# RangkaianESP32___RangkaianDriverMotorDC.net
KiCad netlist of a schematic drawn in EAGLE
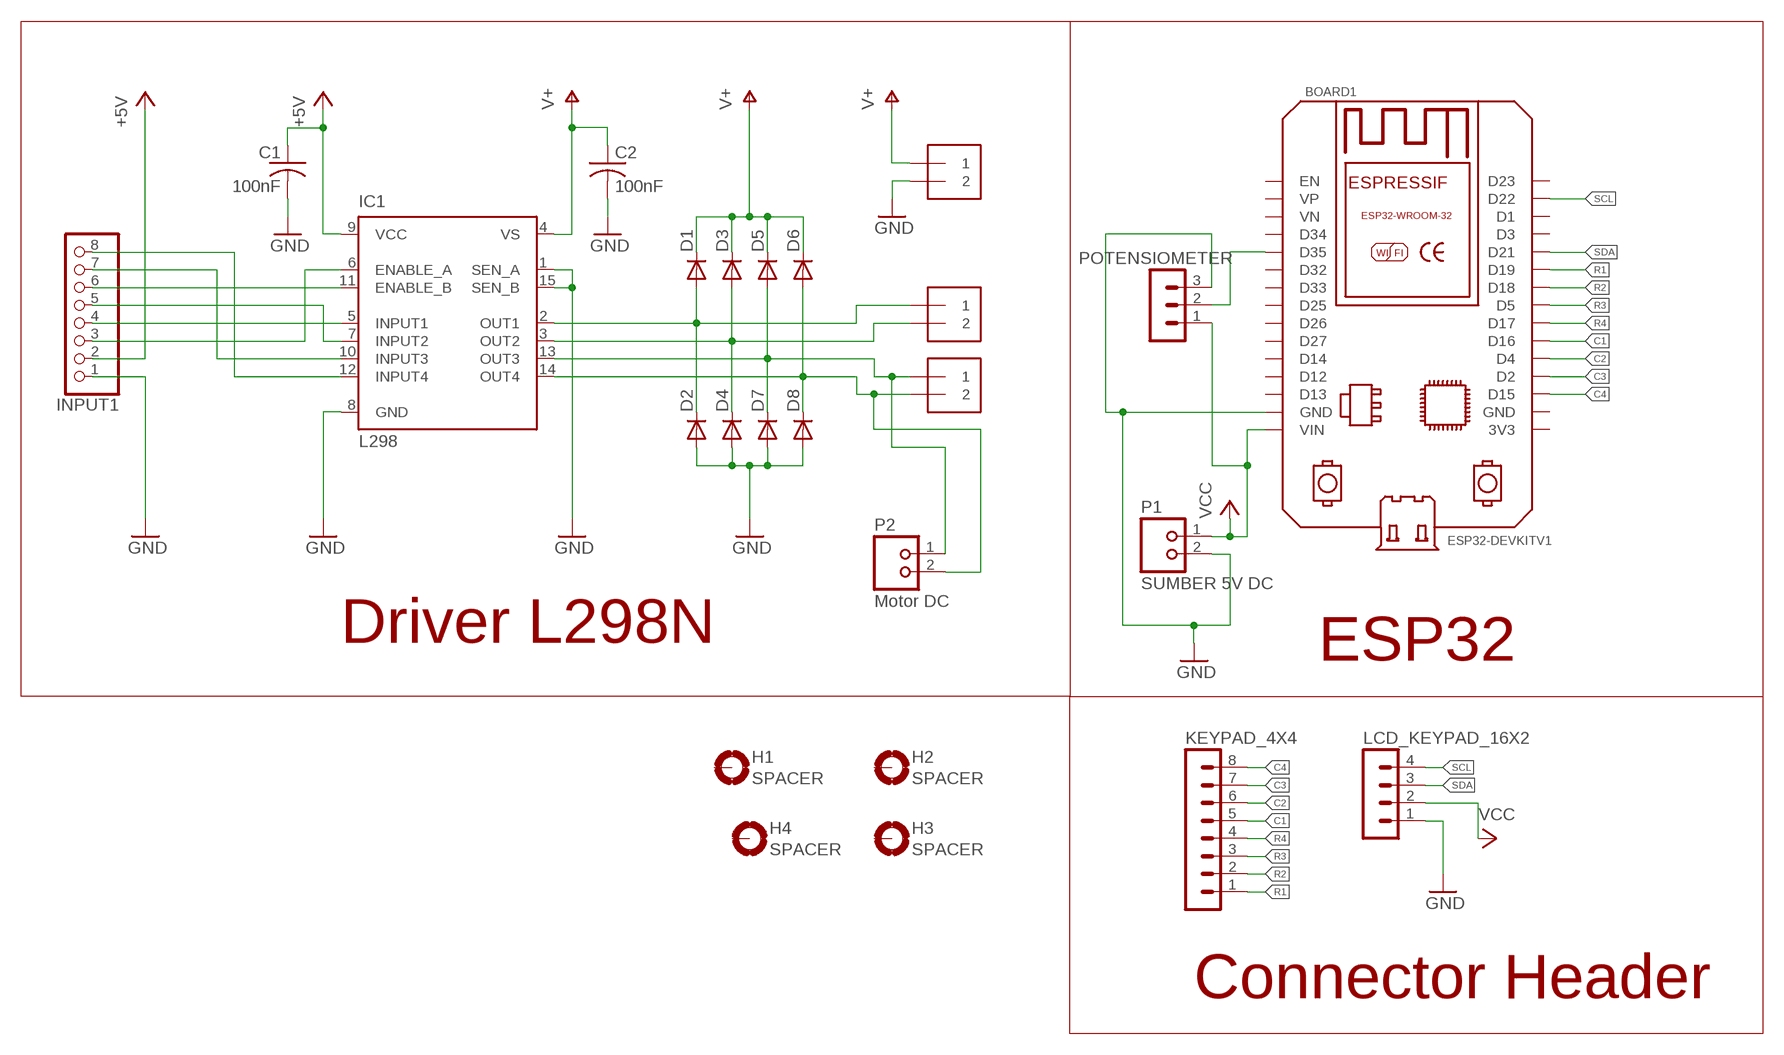
[diagram p0: schematic, sheet 1]

(export (version "E")
  (design (tool "Eeschema 10.0.6"))
  (components
    (comp (ref "BOARD1")
      (value "ESP32DEVKITV1SHRIDATTDUDHAT")
      (footprint "eagle-import:ESP32-DEVKITV1")
      (libsource (lib "eagle-import") (part "ESP32DEVKITV1SHRIDATTDUDHAT"))
    )
    (comp (ref "C1")
      (value "100nF")
      (footprint "eagle-import:C050-024X044")
      (libsource (lib "eagle-import") (part "C-US050-024X044"))
    )
    (comp (ref "C2")
      (value "100nF")
      (footprint "eagle-import:C050-024X044")
      (libsource (lib "eagle-import") (part "C-US050-024X044"))
    )
    (comp (ref "D1")
      (value "DIODE-D-5")
      (footprint "eagle-import:D-5")
      (libsource (lib "eagle-import") (part "DIODE-D-5"))
    )
    (comp (ref "D2")
      (value "DIODE-D-5")
      (footprint "eagle-import:D-5")
      (libsource (lib "eagle-import") (part "DIODE-D-5"))
    )
    (comp (ref "D3")
      (value "DIODE-D-5")
      (footprint "eagle-import:D-5")
      (libsource (lib "eagle-import") (part "DIODE-D-5"))
    )
    (comp (ref "D4")
      (value "DIODE-D-5")
      (footprint "eagle-import:D-5")
      (libsource (lib "eagle-import") (part "DIODE-D-5"))
    )
    (comp (ref "D5")
      (value "DIODE-D-5")
      (footprint "eagle-import:D-5")
      (libsource (lib "eagle-import") (part "DIODE-D-5"))
    )
    (comp (ref "D6")
      (value "DIODE-D-5")
      (footprint "eagle-import:D-5")
      (libsource (lib "eagle-import") (part "DIODE-D-5"))
    )
    (comp (ref "D7")
      (value "DIODE-D-5")
      (footprint "eagle-import:D-5")
      (libsource (lib "eagle-import") (part "DIODE-D-5"))
    )
    (comp (ref "D8")
      (value "DIODE-D-5")
      (footprint "eagle-import:D-5")
      (libsource (lib "eagle-import") (part "DIODE-D-5"))
    )
    (comp (ref "H1")
      (value "SPACER")
      (footprint "eagle-import:3,0-PAD")
      (libsource (lib "eagle-import") (part "SPACER"))
    )
    (comp (ref "H2")
      (value "SPACER")
      (footprint "eagle-import:3,0-PAD")
      (libsource (lib "eagle-import") (part "SPACER"))
    )
    (comp (ref "H3")
      (value "SPACER")
      (footprint "eagle-import:3,0-PAD")
      (libsource (lib "eagle-import") (part "SPACER"))
    )
    (comp (ref "H4")
      (value "SPACER")
      (footprint "eagle-import:3,0-PAD")
      (libsource (lib "eagle-import") (part "SPACER"))
    )
    (comp (ref "IC1")
      (value "L298")
      (footprint "eagle-import:MULTIWATT-15")
      (fields (field (name "MPN") "L298N"))
      (libsource (lib "eagle-import") (part "L298"))
    )
    (comp (ref "INPUT1")
      (value "PINHD-1X8")
      (footprint "eagle-import:1X08")
      (libsource (lib "eagle-import") (part "PINHD-1X8"))
    )
    (comp (ref "KEYPAD_4X4")
      (value "MA08-1")
      (footprint "eagle-import:MA08-1")
      (libsource (lib "eagle-import") (part "MA08-1"))
    )
    (comp (ref "LCD_KEYPAD_16X2")
      (value "MA04-1")
      (footprint "eagle-import:MA04-1")
      (libsource (lib "eagle-import") (part "MA04-1"))
    )
    (comp (ref "OUTPUT1")
      (value "1X2-3.5MM")
      (footprint "eagle-import:1X2-3.5MM")
      (libsource (lib "eagle-import") (part "1X2-3.5MM"))
    )
    (comp (ref "OUTPUT2")
      (value "1X2-3.5MM")
      (footprint "eagle-import:1X2-3.5MM")
      (libsource (lib "eagle-import") (part "1X2-3.5MM"))
    )
    (comp (ref "OUTPUT3")
      (value "1X2-3.5MM")
      (footprint "eagle-import:1X2-3.5MM")
      (libsource (lib "eagle-import") (part "1X2-3.5MM"))
    )
    (comp (ref "P1")
      (value "SUMBER 5V DC")
      (footprint "eagle-import:TERMINAL_2P")
      (libsource (lib "eagle-import") (part "T-BLOCK"))
    )
    (comp (ref "P2")
      (value "Motor DC")
      (footprint "eagle-import:TERMINAL_2P")
      (libsource (lib "eagle-import") (part "T-BLOCK"))
    )
    (comp (ref "POTENSIOMETER")
      (value "MA03-1")
      (footprint "eagle-import:MA03-1")
      (libsource (lib "eagle-import") (part "MA03-1"))
    )
  )
  (nets
    (net (code "1") (name "+5V") (class "Default")
      (node (ref "C1") (pin "1") (pinfunction "1_1") (pintype "passive"))
      (node (ref "IC1") (pin "9") (pinfunction "VCC_9") (pintype "power_in"))
      (node (ref "INPUT1") (pin "2") (pinfunction "2_2") (pintype "passive"))
    )
    (net (code "2") (name "C1") (class "Default")
      (node (ref "BOARD1") (pin "D16") (pinfunction "D16_D16") (pintype "bidirectional"))
      (node (ref "KEYPAD_4X4") (pin "5") (pinfunction "5_5") (pintype "passive"))
    )
    (net (code "3") (name "C2") (class "Default")
      (node (ref "BOARD1") (pin "D4") (pinfunction "D4_D4") (pintype "bidirectional"))
      (node (ref "KEYPAD_4X4") (pin "6") (pinfunction "6_6") (pintype "passive"))
    )
    (net (code "4") (name "C3") (class "Default")
      (node (ref "BOARD1") (pin "D2") (pinfunction "D2_D2") (pintype "bidirectional"))
      (node (ref "KEYPAD_4X4") (pin "7") (pinfunction "7_7") (pintype "passive"))
    )
    (net (code "5") (name "C4") (class "Default")
      (node (ref "BOARD1") (pin "D15") (pinfunction "D15_D15") (pintype "bidirectional"))
      (node (ref "KEYPAD_4X4") (pin "8") (pinfunction "8_8") (pintype "passive"))
    )
    (net (code "6") (name "GND") (class "Default")
      (node (ref "BOARD1") (pin "GND") (pinfunction "GND_GND") (pintype "bidirectional"))
      (node (ref "C1") (pin "2") (pinfunction "2_2") (pintype "passive"))
      (node (ref "C2") (pin "2") (pinfunction "2_2") (pintype "passive"))
      (node (ref "D2") (pin "A") (pinfunction "A_A") (pintype "passive"))
      (node (ref "D4") (pin "A") (pinfunction "A_A") (pintype "passive"))
      (node (ref "D7") (pin "A") (pinfunction "A_A") (pintype "passive"))
      (node (ref "D8") (pin "A") (pinfunction "A_A") (pintype "passive"))
      (node (ref "IC1") (pin "1") (pinfunction "SEN_A_1") (pintype "input"))
      (node (ref "IC1") (pin "15") (pinfunction "SEN_B_15") (pintype "input"))
      (node (ref "IC1") (pin "8") (pinfunction "GND_8") (pintype "power_in"))
      (node (ref "INPUT1") (pin "1") (pinfunction "1_1") (pintype "passive"))
      (node (ref "LCD_KEYPAD_16X2") (pin "1") (pinfunction "1_1") (pintype "passive"))
      (node (ref "OUTPUT1") (pin "2") (pinfunction "2_2") (pintype "passive"))
      (node (ref "P1") (pin "2") (pinfunction "2_2") (pintype "passive"))
      (node (ref "POTENSIOMETER") (pin "3") (pinfunction "3_3") (pintype "passive"))
    )
    (net (code "7") (name "Net-(BOARD1-PadD35)") (class "Default")
      (node (ref "BOARD1") (pin "D35") (pinfunction "D35_D35") (pintype "bidirectional"))
      (node (ref "POTENSIOMETER") (pin "2") (pinfunction "2_2") (pintype "passive"))
    )
    (net (code "8") (name "Net-(IC1-ENABLE_A)") (class "Default")
      (node (ref "IC1") (pin "6") (pinfunction "ENABLE_A_6") (pintype "input"))
      (node (ref "INPUT1") (pin "3") (pinfunction "3_3") (pintype "passive"))
    )
    (net (code "9") (name "Net-(IC1-ENABLE_B)") (class "Default")
      (node (ref "IC1") (pin "11") (pinfunction "ENABLE_B_11") (pintype "input"))
      (node (ref "INPUT1") (pin "6") (pinfunction "6_6") (pintype "passive"))
    )
    (net (code "10") (name "Net-(IC1-INPUT1)") (class "Default")
      (node (ref "IC1") (pin "5") (pinfunction "INPUT1_5") (pintype "input"))
      (node (ref "INPUT1") (pin "4") (pinfunction "4_4") (pintype "passive"))
    )
    (net (code "11") (name "Net-(IC1-INPUT2)") (class "Default")
      (node (ref "IC1") (pin "7") (pinfunction "INPUT2_7") (pintype "input"))
      (node (ref "INPUT1") (pin "5") (pinfunction "5_5") (pintype "passive"))
    )
    (net (code "12") (name "Net-(IC1-INPUT3)") (class "Default")
      (node (ref "IC1") (pin "10") (pinfunction "INPUT3_10") (pintype "input"))
      (node (ref "INPUT1") (pin "7") (pinfunction "7_7") (pintype "passive"))
    )
    (net (code "13") (name "Net-(IC1-INPUT4)") (class "Default")
      (node (ref "IC1") (pin "12") (pinfunction "INPUT4_12") (pintype "input"))
      (node (ref "INPUT1") (pin "8") (pinfunction "8_8") (pintype "passive"))
    )
    (net (code "14") (name "Net-(IC1-OUT1)") (class "Default")
      (node (ref "D1") (pin "A") (pinfunction "A_A") (pintype "passive"))
      (node (ref "D2") (pin "C") (pinfunction "C_C") (pintype "passive"))
      (node (ref "IC1") (pin "2") (pinfunction "OUT1_2") (pintype "output"))
      (node (ref "OUTPUT2") (pin "1") (pinfunction "1_1") (pintype "passive"))
    )
    (net (code "15") (name "Net-(IC1-OUT2)") (class "Default")
      (node (ref "D3") (pin "A") (pinfunction "A_A") (pintype "passive"))
      (node (ref "D4") (pin "C") (pinfunction "C_C") (pintype "passive"))
      (node (ref "IC1") (pin "3") (pinfunction "OUT2_3") (pintype "output"))
      (node (ref "OUTPUT2") (pin "2") (pinfunction "2_2") (pintype "passive"))
    )
    (net (code "16") (name "Net-(IC1-OUT3)") (class "Default")
      (node (ref "D5") (pin "A") (pinfunction "A_A") (pintype "passive"))
      (node (ref "D7") (pin "C") (pinfunction "C_C") (pintype "passive"))
      (node (ref "IC1") (pin "13") (pinfunction "OUT3_13") (pintype "output"))
      (node (ref "OUTPUT3") (pin "1") (pinfunction "1_1") (pintype "passive"))
      (node (ref "P2") (pin "1") (pinfunction "1_1") (pintype "passive"))
    )
    (net (code "17") (name "Net-(IC1-OUT4)") (class "Default")
      (node (ref "D6") (pin "A") (pinfunction "A_A") (pintype "passive"))
      (node (ref "D8") (pin "C") (pinfunction "C_C") (pintype "passive"))
      (node (ref "IC1") (pin "14") (pinfunction "OUT4_14") (pintype "output"))
      (node (ref "OUTPUT3") (pin "2") (pinfunction "2_2") (pintype "passive"))
      (node (ref "P2") (pin "2") (pinfunction "2_2") (pintype "passive"))
    )
    (net (code "18") (name "R1") (class "Default")
      (node (ref "BOARD1") (pin "D19") (pinfunction "D19_D19") (pintype "bidirectional"))
      (node (ref "KEYPAD_4X4") (pin "1") (pinfunction "1_1") (pintype "passive"))
    )
    (net (code "19") (name "R2") (class "Default")
      (node (ref "BOARD1") (pin "D18") (pinfunction "D18_D18") (pintype "bidirectional"))
      (node (ref "KEYPAD_4X4") (pin "2") (pinfunction "2_2") (pintype "passive"))
    )
    (net (code "20") (name "R3") (class "Default")
      (node (ref "BOARD1") (pin "D5") (pinfunction "D5_D5") (pintype "bidirectional"))
      (node (ref "KEYPAD_4X4") (pin "3") (pinfunction "3_3") (pintype "passive"))
    )
    (net (code "21") (name "R4") (class "Default")
      (node (ref "BOARD1") (pin "D17") (pinfunction "D17_D17") (pintype "bidirectional"))
      (node (ref "KEYPAD_4X4") (pin "4") (pinfunction "4_4") (pintype "passive"))
    )
    (net (code "22") (name "SCL") (class "Default")
      (node (ref "BOARD1") (pin "D22") (pinfunction "D22_D22") (pintype "bidirectional"))
      (node (ref "LCD_KEYPAD_16X2") (pin "4") (pinfunction "4_4") (pintype "passive"))
    )
    (net (code "23") (name "SDA") (class "Default")
      (node (ref "BOARD1") (pin "D21") (pinfunction "D21_D21") (pintype "bidirectional"))
      (node (ref "LCD_KEYPAD_16X2") (pin "3") (pinfunction "3_3") (pintype "passive"))
    )
    (net (code "24") (name "V+") (class "Default")
      (node (ref "C2") (pin "1") (pinfunction "1_1") (pintype "passive"))
      (node (ref "D1") (pin "C") (pinfunction "C_C") (pintype "passive"))
      (node (ref "D3") (pin "C") (pinfunction "C_C") (pintype "passive"))
      (node (ref "D5") (pin "C") (pinfunction "C_C") (pintype "passive"))
      (node (ref "D6") (pin "C") (pinfunction "C_C") (pintype "passive"))
      (node (ref "IC1") (pin "4") (pinfunction "VS_4") (pintype "power_in"))
      (node (ref "OUTPUT1") (pin "1") (pinfunction "1_1") (pintype "passive"))
    )
    (net (code "25") (name "VCC") (class "Default")
      (node (ref "BOARD1") (pin "VIN") (pinfunction "VIN_VIN") (pintype "bidirectional"))
      (node (ref "LCD_KEYPAD_16X2") (pin "2") (pinfunction "2_2") (pintype "passive"))
      (node (ref "P1") (pin "1") (pinfunction "1_1") (pintype "passive"))
      (node (ref "POTENSIOMETER") (pin "1") (pinfunction "1_1") (pintype "passive"))
    )
    (net (code "26") (name "unconnected-(BOARD1-GND-PadGND@1)") (class "Default")
      (node (ref "BOARD1") (pin "GND@1") (pinfunction "GND_GND@1") (pintype "bidirectional"))
    )
    (net (code "27") (name "unconnected-(BOARD1-Pad3V3)") (class "Default")
      (node (ref "BOARD1") (pin "3V3") (pinfunction "3V3_3V3") (pintype "bidirectional"))
    )
    (net (code "28") (name "unconnected-(BOARD1-PadD1)") (class "Default")
      (node (ref "BOARD1") (pin "D1") (pinfunction "D1_D1") (pintype "bidirectional"))
    )
    (net (code "29") (name "unconnected-(BOARD1-PadD3)") (class "Default")
      (node (ref "BOARD1") (pin "D3") (pinfunction "D3_D3") (pintype "bidirectional"))
    )
    (net (code "30") (name "unconnected-(BOARD1-PadD12)") (class "Default")
      (node (ref "BOARD1") (pin "D12") (pinfunction "D12_D12") (pintype "bidirectional"))
    )
    (net (code "31") (name "unconnected-(BOARD1-PadD13)") (class "Default")
      (node (ref "BOARD1") (pin "D13") (pinfunction "D13_D13") (pintype "bidirectional"))
    )
    (net (code "32") (name "unconnected-(BOARD1-PadD14)") (class "Default")
      (node (ref "BOARD1") (pin "D14") (pinfunction "D14_D14") (pintype "bidirectional"))
    )
    (net (code "33") (name "unconnected-(BOARD1-PadD23)") (class "Default")
      (node (ref "BOARD1") (pin "D23") (pinfunction "D23_D23") (pintype "bidirectional"))
    )
    (net (code "34") (name "unconnected-(BOARD1-PadD25)") (class "Default")
      (node (ref "BOARD1") (pin "D25") (pinfunction "D25_D25") (pintype "bidirectional"))
    )
    (net (code "35") (name "unconnected-(BOARD1-PadD26)") (class "Default")
      (node (ref "BOARD1") (pin "D26") (pinfunction "D26_D26") (pintype "bidirectional"))
    )
    (net (code "36") (name "unconnected-(BOARD1-PadD27)") (class "Default")
      (node (ref "BOARD1") (pin "D27") (pinfunction "D27_D27") (pintype "bidirectional"))
    )
    (net (code "37") (name "unconnected-(BOARD1-PadD32)") (class "Default")
      (node (ref "BOARD1") (pin "D32") (pinfunction "D32_D32") (pintype "bidirectional"))
    )
    (net (code "38") (name "unconnected-(BOARD1-PadD33)") (class "Default")
      (node (ref "BOARD1") (pin "D33") (pinfunction "D33_D33") (pintype "bidirectional"))
    )
    (net (code "39") (name "unconnected-(BOARD1-PadD34)") (class "Default")
      (node (ref "BOARD1") (pin "D34") (pinfunction "D34_D34") (pintype "bidirectional"))
    )
    (net (code "40") (name "unconnected-(BOARD1-PadEN)") (class "Default")
      (node (ref "BOARD1") (pin "EN") (pinfunction "EN_EN") (pintype "bidirectional"))
    )
    (net (code "41") (name "unconnected-(BOARD1-PadVN)") (class "Default")
      (node (ref "BOARD1") (pin "VN") (pinfunction "VN_VN") (pintype "bidirectional"))
    )
    (net (code "42") (name "unconnected-(BOARD1-PadVP)") (class "Default")
      (node (ref "BOARD1") (pin "VP") (pinfunction "VP_VP") (pintype "bidirectional"))
    )
    (net (code "43") (name "unconnected-(H1-MOUNT-PadB3,0)") (class "Default")
      (node (ref "H1") (pin "B3,0") (pinfunction "MOUNT_B3,0") (pintype "passive"))
    )
    (net (code "44") (name "unconnected-(H2-MOUNT-PadB3,0)") (class "Default")
      (node (ref "H2") (pin "B3,0") (pinfunction "MOUNT_B3,0") (pintype "passive"))
    )
    (net (code "45") (name "unconnected-(H3-MOUNT-PadB3,0)") (class "Default")
      (node (ref "H3") (pin "B3,0") (pinfunction "MOUNT_B3,0") (pintype "passive"))
    )
    (net (code "46") (name "unconnected-(H4-MOUNT-PadB3,0)") (class "Default")
      (node (ref "H4") (pin "B3,0") (pinfunction "MOUNT_B3,0") (pintype "passive"))
    )
  )
)
